# ESP32S3.net
KiCad netlist of a schematic drawn in Altium Designer
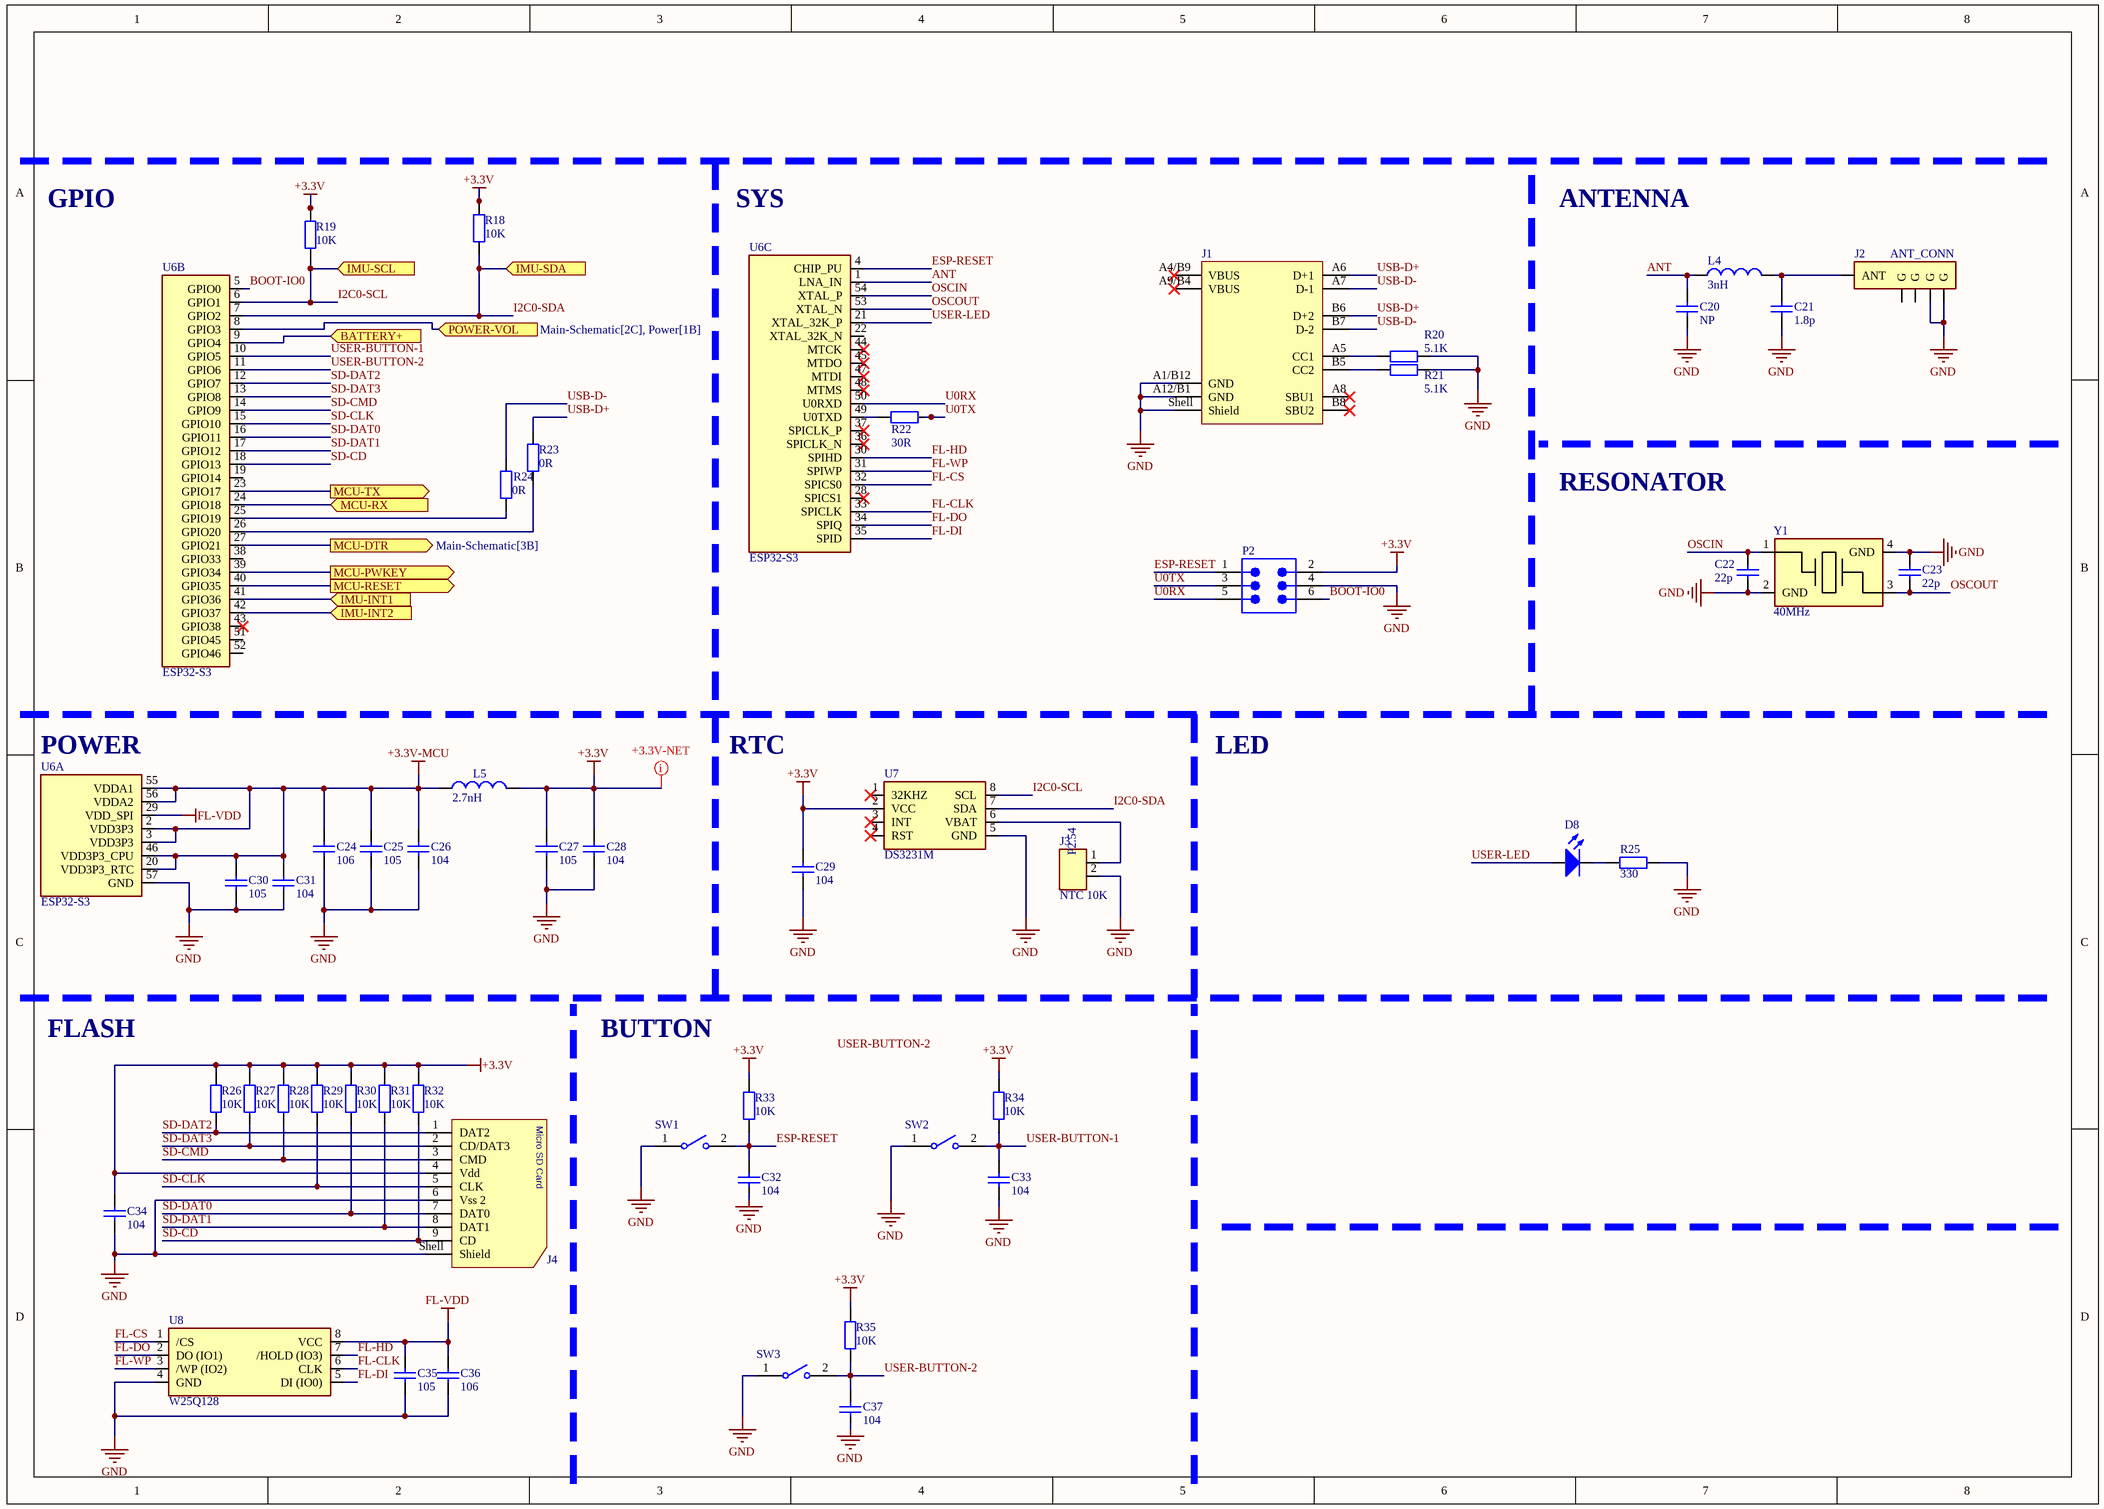
[diagram p0: ESP32S3.SchDoc]

(export (version "E")
  (design (tool "Eeschema 10.0.6"))
  (components
    (comp (ref "C20")
      (value "NP")
      (footprint "CAP_0603")
      (description "Non-polarized capacitor")
      (libsource (lib "Capacitor") (part "Cap_NP"))
    )
    (comp (ref "C21")
      (value "1.8p")
      (footprint "CAP_0603")
      (description "Non-polarized capacitor")
      (libsource (lib "Capacitor") (part "Cap_NP"))
    )
    (comp (ref "C22")
      (value "22p")
      (footprint "CAP_0603")
      (description "Non-polarized capacitor")
      (libsource (lib "Capacitor") (part "Cap_NP"))
    )
    (comp (ref "C23")
      (value "22p")
      (footprint "CAP_0603")
      (description "Non-polarized capacitor")
      (libsource (lib "Capacitor") (part "Cap_NP"))
    )
    (comp (ref "C24")
      (value "106")
      (footprint "CAP_0603")
      (description "Non-polarized capacitor")
      (libsource (lib "Capacitor") (part "Cap_NP"))
    )
    (comp (ref "C25")
      (value "105")
      (footprint "CAP_0603")
      (description "Non-polarized capacitor")
      (libsource (lib "Capacitor") (part "Cap_NP"))
    )
    (comp (ref "C26")
      (value "104")
      (footprint "CAP_0603")
      (description "Non-polarized capacitor")
      (libsource (lib "Capacitor") (part "Cap_NP"))
    )
    (comp (ref "C27")
      (value "105")
      (footprint "CAP_0603")
      (description "Non-polarized capacitor")
      (libsource (lib "Capacitor") (part "Cap_NP"))
    )
    (comp (ref "C28")
      (value "104")
      (footprint "CAP_0603")
      (description "Non-polarized capacitor")
      (libsource (lib "Capacitor") (part "Cap_NP"))
    )
    (comp (ref "C29")
      (value "104")
      (footprint "CAP_0603")
      (description "Non-polarized capacitor")
      (libsource (lib "Capacitor") (part "Cap_NP"))
    )
    (comp (ref "C30")
      (value "105")
      (footprint "CAP_0603")
      (description "Non-polarized capacitor")
      (libsource (lib "Capacitor") (part "Cap_NP"))
    )
    (comp (ref "C31")
      (value "104")
      (footprint "CAP_0603")
      (description "Non-polarized capacitor")
      (libsource (lib "Capacitor") (part "Cap_NP"))
    )
    (comp (ref "C32")
      (value "104")
      (footprint "CAP_0603")
      (description "Non-polarized capacitor")
      (libsource (lib "Capacitor") (part "Cap_NP"))
    )
    (comp (ref "C33")
      (value "104")
      (footprint "CAP_0603")
      (description "Non-polarized capacitor")
      (libsource (lib "Capacitor") (part "Cap_NP"))
    )
    (comp (ref "C34")
      (value "104")
      (footprint "CAP_0603")
      (description "Non-polarized capacitor")
      (libsource (lib "Capacitor") (part "Cap_NP"))
    )
    (comp (ref "C35")
      (value "105")
      (footprint "CAP_0603")
      (description "Non-polarized capacitor")
      (libsource (lib "Capacitor") (part "Cap_NP"))
    )
    (comp (ref "C36")
      (value "106")
      (footprint "CAP_0603")
      (description "Non-polarized capacitor")
      (libsource (lib "Capacitor") (part "Cap_NP"))
    )
    (comp (ref "C37")
      (value "104")
      (footprint "CAP_0603")
      (description "Non-polarized capacitor")
      (libsource (lib "Capacitor") (part "Cap_NP"))
    )
    (comp (ref "D8")
      (value "~")
      (footprint "LED-0805-Red")
      (description "Light Emitting Diode")
      (libsource (lib "Diode") (part "LED"))
    )
    (comp (ref "J1")
      (value "629722000214")
      (footprint "629722000214")
      (description "WR-COM USB 2.0 Type C Receptacle Horizontal SMT")
      (fields (field (name "MANUFACTURER") "Wurth Elektronik"))
      (libsource (lib "WE - Electromechanical Components") (part "USB 2.0_Type C_Receptacle_1 Port_629722000214"))
    )
    (comp (ref "J2")
      (value "ANT_CONN")
      (footprint "IPEX")
      (description "ATENNA PIN 1")
      (libsource (lib "Connector") (part "ANT_CONN"))
    )
    (comp (ref "J3")
      (value "NTC 10K")
      (footprint "XH2.54M-2")
      (libsource (lib "Connector") (part "Conn_Cai_2P_2.54"))
    )
    (comp (ref "J4")
      (value "693071040911")
      (footprint "693071040911")
      (description "WR-CRD SD Card Connector Push & Push Socket, 9 pins")
      (fields (field (name "MANUFACTURER") "Wurth Elektronik"))
      (libsource (lib "WE - Electromechanical Components") (part "Micro SD Card Socket_693071040911"))
    )
    (comp (ref "L4")
      (value "3nH")
      (footprint "INDC-0805")
      (description "Inductor")
      (fields (field (name "PUBLISHER") "Altium Limited"))
      (libsource (lib "Inductor") (part "Inductor"))
    )
    (comp (ref "L5")
      (value "2.7nH")
      (footprint "INDC-0805")
      (description "Inductor")
      (fields (field (name "PUBLISHER") "Altium Limited"))
      (libsource (lib "Inductor") (part "Inductor"))
    )
    (comp (ref "P2")
      (value "61200621621")
      (footprint "61200621621")
      (description "WR-BHD Male Box Header, THT Straight, pitch 2.54 mm, 2 Rows, 6 Pins")
      (fields (field (name "MANUFACTURER") "Wurth Elektronik"))
      (libsource (lib "WE - Electromechanical Components") (part "Header_Male_2R_06P"))
    )
    (comp (ref "R18") (value "10K") (footprint "RES_0603") (libsource (lib "Resistor") (part "Resistor")))
    (comp (ref "R19") (value "10K") (footprint "RES_0603") (libsource (lib "Resistor") (part "Resistor")))
    (comp (ref "R20") (value "5.1K") (footprint "RES_0603") (libsource (lib "") (part "Resistor_1")))
    (comp (ref "R21") (value "5.1K") (footprint "RES_0603") (libsource (lib "") (part "Resistor_1")))
    (comp (ref "R22") (value "30R") (footprint "RES_0603") (libsource (lib "") (part "Resistor_1")))
    (comp (ref "R23") (value "0R") (footprint "RES_0603") (libsource (lib "Resistor") (part "Resistor")))
    (comp (ref "R24") (value "0R") (footprint "RES_0603") (libsource (lib "Resistor") (part "Resistor")))
    (comp (ref "R25") (value "330") (footprint "RES_0603") (libsource (lib "") (part "Resistor_1")))
    (comp (ref "R26") (value "10K") (footprint "RES_0603") (libsource (lib "Resistor") (part "Resistor")))
    (comp (ref "R27") (value "10K") (footprint "RES_0603") (libsource (lib "Resistor") (part "Resistor")))
    (comp (ref "R28") (value "10K") (footprint "RES_0603") (libsource (lib "Resistor") (part "Resistor")))
    (comp (ref "R29") (value "10K") (footprint "RES_0603") (libsource (lib "Resistor") (part "Resistor")))
    (comp (ref "R30") (value "10K") (footprint "RES_0603") (libsource (lib "Resistor") (part "Resistor")))
    (comp (ref "R31") (value "10K") (footprint "RES_0603") (libsource (lib "Resistor") (part "Resistor")))
    (comp (ref "R32") (value "10K") (footprint "RES_0603") (libsource (lib "Resistor") (part "Resistor")))
    (comp (ref "R33") (value "10K") (footprint "RES_0603") (libsource (lib "Resistor") (part "Resistor")))
    (comp (ref "R34") (value "10K") (footprint "RES_0603") (libsource (lib "Resistor") (part "Resistor")))
    (comp (ref "R35") (value "10K") (footprint "RES_0603") (libsource (lib "Resistor") (part "Resistor")))
    (comp (ref "SW1")
      (value "434121050816")
      (footprint "434121050816")
      (description "WS-TASV SMT Tact Switch, 6mm x 3.5mm, 160gf, SPST-NO, 12V, 50mA")
      (fields (field (name "MANUFACTURER") "Wurth Elektronik"))
      (libsource (lib "WE - Electromechanical Components") (part "SPST-NO_2P"))
    )
    (comp (ref "SW2")
      (value "434121050816")
      (footprint "434121050816")
      (description "WS-TASV SMT Tact Switch, 6mm x 3.5mm, 160gf, SPST-NO, 12V, 50mA")
      (fields (field (name "MANUFACTURER") "Wurth Elektronik"))
      (libsource (lib "WE - Electromechanical Components") (part "SPST-NO_2P"))
    )
    (comp (ref "SW3")
      (value "434121050816")
      (footprint "434121050816")
      (description "WS-TASV SMT Tact Switch, 6mm x 3.5mm, 160gf, SPST-NO, 12V, 50mA")
      (fields (field (name "MANUFACTURER") "Wurth Elektronik"))
      (libsource (lib "WE - Electromechanical Components") (part "SPST-NO_2P"))
    )
    (comp (ref "U6") (value "ESP32-S3") (footprint "QFN56") (libsource (lib "IC") (part "ESP32-S3")))
    (comp (ref "U7")
      (value "DS3231M")
      (footprint "SOP8-P1.27")
      (description "I2C realtime clock (RTC)")
      (libsource (lib "IC") (part "DS3231M"))
    )
    (comp (ref "U8")
      (value "W25Q128")
      (footprint "SOIC127P790X216-8N")
      (description "256M-bit (32MB) Serial Flash memory")
      (libsource (lib "IC") (part "W25Q256JV"))
    )
    (comp (ref "Y1") (value "40MHz") (footprint "Y-3225") (libsource (lib "IC") (part "Resonator")))
  )
  (nets
    (net (code "1") (name "+3.3V") (class "Default")
      (node (ref "C27") (pin "2") (pinfunction "2_2") (pintype "passive"))
      (node (ref "C28") (pin "2") (pinfunction "2_2") (pintype "passive"))
      (node (ref "C29") (pin "1") (pinfunction "1_1") (pintype "passive"))
      (node (ref "C34") (pin "2") (pinfunction "2_2") (pintype "passive"))
      (node (ref "J4") (pin "4") (pinfunction "Vdd_4") (pintype "passive"))
      (node (ref "L5") (pin "2") (pinfunction "2_2") (pintype "passive"))
      (node (ref "P2") (pin "2") (pinfunction "2_2") (pintype "passive"))
      (node (ref "R18") (pin "2") (pinfunction "2_2") (pintype "passive"))
      (node (ref "R19") (pin "2") (pinfunction "2_2") (pintype "passive"))
      (node (ref "R26") (pin "2") (pinfunction "2_2") (pintype "passive"))
      (node (ref "R27") (pin "2") (pinfunction "2_2") (pintype "passive"))
      (node (ref "R28") (pin "2") (pinfunction "2_2") (pintype "passive"))
      (node (ref "R29") (pin "2") (pinfunction "2_2") (pintype "passive"))
      (node (ref "R30") (pin "2") (pinfunction "2_2") (pintype "passive"))
      (node (ref "R31") (pin "2") (pinfunction "2_2") (pintype "passive"))
      (node (ref "R32") (pin "2") (pinfunction "2_2") (pintype "passive"))
      (node (ref "R33") (pin "2") (pinfunction "2_2") (pintype "passive"))
      (node (ref "R34") (pin "2") (pinfunction "2_2") (pintype "passive"))
      (node (ref "R35") (pin "2") (pinfunction "2_2") (pintype "passive"))
      (node (ref "U7") (pin "2") (pinfunction "VCC_2") (pintype "passive"))
    )
    (net (code "2") (name "+3.3V-MCU") (class "Default")
      (node (ref "C24") (pin "2") (pinfunction "2_2") (pintype "passive"))
      (node (ref "C25") (pin "2") (pinfunction "2_2") (pintype "passive"))
      (node (ref "C26") (pin "2") (pinfunction "2_2") (pintype "passive"))
      (node (ref "C30") (pin "2") (pinfunction "2_2") (pintype "passive"))
      (node (ref "C31") (pin "2") (pinfunction "2_2") (pintype "passive"))
      (node (ref "L5") (pin "1") (pinfunction "1_1") (pintype "passive"))
      (node (ref "U6") (pin "2") (pinfunction "VDD3P3_2") (pintype "passive"))
      (node (ref "U6") (pin "20") (pinfunction "VDD3P3_RTC_20") (pintype "passive"))
      (node (ref "U6") (pin "3") (pinfunction "VDD3P3_3") (pintype "passive"))
      (node (ref "U6") (pin "46") (pinfunction "VDD3P3_CPU_46") (pintype "passive"))
      (node (ref "U6") (pin "55") (pinfunction "VDDA1_55") (pintype "passive"))
      (node (ref "U6") (pin "56") (pinfunction "VDDA2_56") (pintype "passive"))
    )
    (net (code "3") (name "/ANT") (class "Default")
      (node (ref "C20") (pin "2") (pinfunction "2_2") (pintype "passive"))
      (node (ref "L4") (pin "1") (pinfunction "1_1") (pintype "passive"))
      (node (ref "U6") (pin "1") (pinfunction "LNA_IN_1") (pintype "passive"))
    )
    (net (code "4") (name "/BATTERY+") (class "Default")
      (node (ref "U6") (pin "9") (pinfunction "GPIO4_9") (pintype "passive"))
    )
    (net (code "5") (name "/BOOT-IO0") (class "Default")
      (node (ref "P2") (pin "6") (pinfunction "6_6") (pintype "passive"))
      (node (ref "U6") (pin "5") (pinfunction "GPIO0_5") (pintype "passive"))
    )
    (net (code "6") (name "/ESP-RESET") (class "Default")
      (node (ref "C32") (pin "1") (pinfunction "1_1") (pintype "passive"))
      (node (ref "P2") (pin "1") (pinfunction "1_1") (pintype "passive"))
      (node (ref "R33") (pin "1") (pinfunction "1_1") (pintype "passive"))
      (node (ref "SW1") (pin "2") (pinfunction "2_2") (pintype "passive"))
      (node (ref "U6") (pin "4") (pinfunction "CHIP_PU_4") (pintype "passive"))
    )
    (net (code "7") (name "/FL-CLK") (class "Default")
      (node (ref "U6") (pin "33") (pinfunction "SPICLK_33") (pintype "passive"))
      (node (ref "U8") (pin "6") (pinfunction "CLK_6") (pintype "passive"))
    )
    (net (code "8") (name "/FL-CS") (class "Default")
      (node (ref "U6") (pin "32") (pinfunction "SPICS0_32") (pintype "passive"))
      (node (ref "U8") (pin "1") (pinfunction "/CS_1") (pintype "passive"))
    )
    (net (code "9") (name "/FL-DI") (class "Default")
      (node (ref "U6") (pin "35") (pinfunction "SPID_35") (pintype "passive"))
      (node (ref "U8") (pin "5") (pinfunction "DI_(IO0)_5") (pintype "passive"))
    )
    (net (code "10") (name "/FL-DO") (class "Default")
      (node (ref "U6") (pin "34") (pinfunction "SPIQ_34") (pintype "passive"))
      (node (ref "U8") (pin "2") (pinfunction "DO_(IO1)_2") (pintype "passive"))
    )
    (net (code "11") (name "/FL-HD") (class "Default")
      (node (ref "U6") (pin "30") (pinfunction "SPIHD_30") (pintype "passive"))
      (node (ref "U8") (pin "7") (pinfunction "/HOLD_(IO3)_7") (pintype "passive"))
    )
    (net (code "12") (name "/FL-WP") (class "Default")
      (node (ref "U6") (pin "31") (pinfunction "SPIWP_31") (pintype "passive"))
      (node (ref "U8") (pin "3") (pinfunction "/WP_(IO2)_3") (pintype "passive"))
    )
    (net (code "13") (name "/I2C0-SCL") (class "Default")
      (node (ref "R19") (pin "1") (pinfunction "1_1") (pintype "passive"))
      (node (ref "U6") (pin "6") (pinfunction "GPIO1_6") (pintype "passive"))
      (node (ref "U7") (pin "8") (pinfunction "SCL_8") (pintype "passive"))
    )
    (net (code "14") (name "/I2C0-SDA") (class "Default")
      (node (ref "R18") (pin "1") (pinfunction "1_1") (pintype "passive"))
      (node (ref "U6") (pin "7") (pinfunction "GPIO2_7") (pintype "passive"))
      (node (ref "U7") (pin "7") (pinfunction "SDA_7") (pintype "passive"))
    )
    (net (code "15") (name "/IMU-INT1") (class "Default")
      (node (ref "U6") (pin "41") (pinfunction "GPIO36_41") (pintype "passive"))
    )
    (net (code "16") (name "/IMU-INT2") (class "Default")
      (node (ref "U6") (pin "42") (pinfunction "GPIO37_42") (pintype "passive"))
    )
    (net (code "17") (name "/MCU-DTR") (class "Default")
      (node (ref "U6") (pin "27") (pinfunction "GPIO21_27") (pintype "passive"))
    )
    (net (code "18") (name "/MCU-PWKEY") (class "Default")
      (node (ref "U6") (pin "39") (pinfunction "GPIO34_39") (pintype "passive"))
    )
    (net (code "19") (name "/MCU-RESET") (class "Default")
      (node (ref "U6") (pin "40") (pinfunction "GPIO35_40") (pintype "passive"))
    )
    (net (code "20") (name "/MCU-RX") (class "Default")
      (node (ref "U6") (pin "24") (pinfunction "GPIO18_24") (pintype "passive"))
    )
    (net (code "21") (name "/MCU-TX") (class "Default")
      (node (ref "U6") (pin "23") (pinfunction "GPIO17_23") (pintype "passive"))
    )
    (net (code "22") (name "/OSCIN") (class "Default")
      (node (ref "C22") (pin "2") (pinfunction "2_2") (pintype "passive"))
      (node (ref "U6") (pin "54") (pinfunction "XTAL_P_54") (pintype "passive"))
      (node (ref "Y1") (pin "1") (pinfunction "OSCIN_1") (pintype "passive"))
    )
    (net (code "23") (name "/OSCOUT") (class "Default")
      (node (ref "C23") (pin "1") (pinfunction "1_1") (pintype "passive"))
      (node (ref "U6") (pin "53") (pinfunction "XTAL_N_53") (pintype "passive"))
      (node (ref "Y1") (pin "3") (pinfunction "OSCOUT_3") (pintype "passive"))
    )
    (net (code "24") (name "/POWER-VOL") (class "Default")
      (node (ref "U6") (pin "8") (pinfunction "GPIO3_8") (pintype "passive"))
    )
    (net (code "25") (name "/SD-CD") (class "Default")
      (node (ref "J4") (pin "9") (pinfunction "CD_9") (pintype "passive"))
      (node (ref "R32") (pin "1") (pinfunction "1_1") (pintype "passive"))
      (node (ref "U6") (pin "18") (pinfunction "GPIO13_18") (pintype "passive"))
    )
    (net (code "26") (name "/SD-CLK") (class "Default")
      (node (ref "J4") (pin "5") (pinfunction "CLK_5") (pintype "passive"))
      (node (ref "R29") (pin "1") (pinfunction "1_1") (pintype "passive"))
      (node (ref "U6") (pin "15") (pinfunction "GPIO10_15") (pintype "passive"))
    )
    (net (code "27") (name "/SD-CMD") (class "Default")
      (node (ref "J4") (pin "3") (pinfunction "CMD_3") (pintype "passive"))
      (node (ref "R28") (pin "1") (pinfunction "1_1") (pintype "passive"))
      (node (ref "U6") (pin "14") (pinfunction "GPIO9_14") (pintype "passive"))
    )
    (net (code "28") (name "/SD-DAT0") (class "Default")
      (node (ref "J4") (pin "7") (pinfunction "DAT0_7") (pintype "passive"))
      (node (ref "R30") (pin "1") (pinfunction "1_1") (pintype "passive"))
      (node (ref "U6") (pin "16") (pinfunction "GPIO11_16") (pintype "passive"))
    )
    (net (code "29") (name "/SD-DAT1") (class "Default")
      (node (ref "J4") (pin "8") (pinfunction "DAT1_8") (pintype "passive"))
      (node (ref "R31") (pin "1") (pinfunction "1_1") (pintype "passive"))
      (node (ref "U6") (pin "17") (pinfunction "GPIO12_17") (pintype "passive"))
    )
    (net (code "30") (name "/SD-DAT2") (class "Default")
      (node (ref "J4") (pin "1") (pinfunction "DAT2_1") (pintype "passive"))
      (node (ref "R26") (pin "1") (pinfunction "1_1") (pintype "passive"))
      (node (ref "U6") (pin "12") (pinfunction "GPIO7_12") (pintype "passive"))
    )
    (net (code "31") (name "/SD-DAT3") (class "Default")
      (node (ref "J4") (pin "2") (pinfunction "CD/DAT3_2") (pintype "passive"))
      (node (ref "R27") (pin "1") (pinfunction "1_1") (pintype "passive"))
      (node (ref "U6") (pin "13") (pinfunction "GPIO8_13") (pintype "passive"))
    )
    (net (code "32") (name "/U0RX") (class "Default")
      (node (ref "P2") (pin "5") (pinfunction "5_5") (pintype "passive"))
      (node (ref "U6") (pin "50") (pinfunction "U0RXD_50") (pintype "passive"))
    )
    (net (code "33") (name "/U0TX") (class "Default")
      (node (ref "P2") (pin "3") (pinfunction "3_3") (pintype "passive"))
      (node (ref "R22") (pin "2") (pinfunction "2_2") (pintype "passive"))
    )
    (net (code "34") (name "/USB-D+") (class "Default")
      (node (ref "J1") (pin "A6") (pinfunction "D+1_A6") (pintype "passive"))
      (node (ref "J1") (pin "B6") (pinfunction "D+2_B6") (pintype "passive"))
      (node (ref "R23") (pin "2") (pinfunction "2_2") (pintype "passive"))
    )
    (net (code "35") (name "/USB-D-") (class "Default")
      (node (ref "J1") (pin "A7") (pinfunction "D-1_A7") (pintype "passive"))
      (node (ref "J1") (pin "B7") (pinfunction "D-2_B7") (pintype "passive"))
      (node (ref "R24") (pin "2") (pinfunction "2_2") (pintype "passive"))
    )
    (net (code "36") (name "/USER-BUTTON-1") (class "Default")
      (node (ref "C33") (pin "1") (pinfunction "1_1") (pintype "passive"))
      (node (ref "R34") (pin "1") (pinfunction "1_1") (pintype "passive"))
      (node (ref "SW2") (pin "2") (pinfunction "2_2") (pintype "passive"))
      (node (ref "U6") (pin "10") (pinfunction "GPIO5_10") (pintype "passive"))
    )
    (net (code "37") (name "/USER-BUTTON-2") (class "Default")
      (node (ref "C37") (pin "1") (pinfunction "1_1") (pintype "passive"))
      (node (ref "R35") (pin "1") (pinfunction "1_1") (pintype "passive"))
      (node (ref "SW3") (pin "2") (pinfunction "2_2") (pintype "passive"))
      (node (ref "U6") (pin "11") (pinfunction "GPIO6_11") (pintype "passive"))
    )
    (net (code "38") (name "/USER-LED") (class "Default")
      (node (ref "D8") (pin "1") (pinfunction "A_1") (pintype "passive"))
      (node (ref "U6") (pin "21") (pinfunction "XTAL_32K_P_21") (pintype "passive"))
    )
    (net (code "39") (name "FL-VDD") (class "Default")
      (node (ref "C35") (pin "2") (pinfunction "2_2") (pintype "passive"))
      (node (ref "C36") (pin "2") (pinfunction "2_2") (pintype "passive"))
      (node (ref "U6") (pin "29") (pinfunction "VDD_SPI_29") (pintype "passive"))
      (node (ref "U8") (pin "8") (pinfunction "VCC_8") (pintype "passive"))
    )
    (net (code "40") (name "GND") (class "Default")
      (node (ref "C20") (pin "1") (pinfunction "1_1") (pintype "passive"))
      (node (ref "C21") (pin "1") (pinfunction "1_1") (pintype "passive"))
      (node (ref "C22") (pin "1") (pinfunction "1_1") (pintype "passive"))
      (node (ref "C23") (pin "2") (pinfunction "2_2") (pintype "passive"))
      (node (ref "C24") (pin "1") (pinfunction "1_1") (pintype "passive"))
      (node (ref "C25") (pin "1") (pinfunction "1_1") (pintype "passive"))
      (node (ref "C26") (pin "1") (pinfunction "1_1") (pintype "passive"))
      (node (ref "C27") (pin "1") (pinfunction "1_1") (pintype "passive"))
      (node (ref "C28") (pin "1") (pinfunction "1_1") (pintype "passive"))
      (node (ref "C29") (pin "2") (pinfunction "2_2") (pintype "passive"))
      (node (ref "C30") (pin "1") (pinfunction "1_1") (pintype "passive"))
      (node (ref "C31") (pin "1") (pinfunction "1_1") (pintype "passive"))
      (node (ref "C32") (pin "2") (pinfunction "2_2") (pintype "passive"))
      (node (ref "C33") (pin "2") (pinfunction "2_2") (pintype "passive"))
      (node (ref "C34") (pin "1") (pinfunction "1_1") (pintype "passive"))
      (node (ref "C35") (pin "1") (pinfunction "1_1") (pintype "passive"))
      (node (ref "C36") (pin "1") (pinfunction "1_1") (pintype "passive"))
      (node (ref "C37") (pin "2") (pinfunction "2_2") (pintype "passive"))
      (node (ref "J1") (pin "A1/B12") (pinfunction "GND_A1/B12") (pintype "passive"))
      (node (ref "J1") (pin "A12/B1") (pinfunction "GND_A12/B1") (pintype "passive"))
      (node (ref "J1") (pin "Shell") (pinfunction "Shield_Shell") (pintype "passive"))
      (node (ref "J2") (pin "4") (pinfunction "G_4") (pintype "passive"))
      (node (ref "J2") (pin "5") (pinfunction "G_5") (pintype "passive"))
      (node (ref "J3") (pin "2") (pintype "passive"))
      (node (ref "J4") (pin "6") (pinfunction "Vss_2_6") (pintype "passive"))
      (node (ref "J4") (pin "Shell") (pinfunction "Shield_Shell") (pintype "passive"))
      (node (ref "P2") (pin "4") (pinfunction "4_4") (pintype "passive"))
      (node (ref "R20") (pin "2") (pinfunction "2_2") (pintype "passive"))
      (node (ref "R21") (pin "2") (pinfunction "2_2") (pintype "passive"))
      (node (ref "R25") (pin "2") (pinfunction "2_2") (pintype "passive"))
      (node (ref "SW1") (pin "1") (pinfunction "1_1") (pintype "passive"))
      (node (ref "SW2") (pin "1") (pinfunction "1_1") (pintype "passive"))
      (node (ref "SW3") (pin "1") (pinfunction "1_1") (pintype "passive"))
      (node (ref "U6") (pin "57") (pinfunction "GND_57") (pintype "passive"))
      (node (ref "U7") (pin "5") (pinfunction "GND_5") (pintype "passive"))
      (node (ref "U8") (pin "4") (pinfunction "GND_4") (pintype "passive"))
      (node (ref "Y1") (pin "2") (pinfunction "GND_2") (pintype "passive"))
      (node (ref "Y1") (pin "4") (pinfunction "GND_4") (pintype "passive"))
    )
    (net (code "41") (name "Net-(D8-K)") (class "Default")
      (node (ref "D8") (pin "2") (pinfunction "K_2") (pintype "passive"))
      (node (ref "R25") (pin "1") (pinfunction "1_1") (pintype "passive"))
    )
    (net (code "42") (name "Net-(J1-CC1)") (class "Default")
      (node (ref "J1") (pin "A5") (pinfunction "CC1_A5") (pintype "passive"))
      (node (ref "R20") (pin "1") (pinfunction "1_1") (pintype "passive"))
    )
    (net (code "43") (name "Net-(J1-CC2)") (class "Default")
      (node (ref "J1") (pin "B5") (pinfunction "CC2_B5") (pintype "passive"))
      (node (ref "R21") (pin "1") (pinfunction "1_1") (pintype "passive"))
    )
    (net (code "44") (name "Net-(J2-ANT)") (class "Default")
      (node (ref "C21") (pin "2") (pinfunction "2_2") (pintype "passive"))
      (node (ref "J2") (pin "1") (pinfunction "ANT_1") (pintype "passive"))
      (node (ref "L4") (pin "2") (pinfunction "2_2") (pintype "passive"))
    )
    (net (code "45") (name "Net-(U6B-GPIO19)") (class "Default")
      (node (ref "R24") (pin "1") (pinfunction "1_1") (pintype "passive"))
      (node (ref "U6") (pin "25") (pinfunction "GPIO19_25") (pintype "passive"))
    )
    (net (code "46") (name "Net-(U6B-GPIO20)") (class "Default")
      (node (ref "R23") (pin "1") (pinfunction "1_1") (pintype "passive"))
      (node (ref "U6") (pin "26") (pinfunction "GPIO20_26") (pintype "passive"))
    )
    (net (code "47") (name "Net-(U6C-U0TXD)") (class "Default")
      (node (ref "R22") (pin "1") (pinfunction "1_1") (pintype "passive"))
      (node (ref "U6") (pin "49") (pinfunction "U0TXD_49") (pintype "passive"))
    )
    (net (code "48") (name "Net-(U7-VBAT)") (class "Default")
      (node (ref "J3") (pin "1") (pintype "passive"))
      (node (ref "U7") (pin "6") (pinfunction "VBAT_6") (pintype "passive"))
    )
    (net (code "49") (name "unconnected-(J1-SBU1-PadA8)") (class "Default")
      (node (ref "J1") (pin "A8") (pinfunction "SBU1_A8") (pintype "passive+no_connect"))
    )
    (net (code "50") (name "unconnected-(J1-SBU2-PadB8)") (class "Default")
      (node (ref "J1") (pin "B8") (pinfunction "SBU2_B8") (pintype "passive+no_connect"))
    )
    (net (code "51") (name "unconnected-(J1-VBUS-PadA4{slash}B9)") (class "Default")
      (node (ref "J1") (pin "A4/B9") (pinfunction "VBUS_A4/B9") (pintype "passive+no_connect"))
    )
    (net (code "52") (name "unconnected-(J1-VBUS-PadA9{slash}B4)") (class "Default")
      (node (ref "J1") (pin "A9/B4") (pinfunction "VBUS_A9/B4") (pintype "passive+no_connect"))
    )
    (net (code "53") (name "unconnected-(J2-G-Pad2)") (class "Default")
      (node (ref "J2") (pin "2") (pinfunction "G_2") (pintype "passive"))
    )
    (net (code "54") (name "unconnected-(J2-G-Pad3)") (class "Default")
      (node (ref "J2") (pin "3") (pinfunction "G_3") (pintype "passive"))
    )
    (net (code "55") (name "unconnected-(U6B-GPIO14-Pad19)") (class "Default")
      (node (ref "U6") (pin "19") (pinfunction "GPIO14_19") (pintype "passive"))
    )
    (net (code "56") (name "unconnected-(U6B-GPIO33-Pad38)") (class "Default")
      (node (ref "U6") (pin "38") (pinfunction "GPIO33_38") (pintype "passive"))
    )
    (net (code "57") (name "unconnected-(U6B-GPIO38-Pad43)") (class "Default")
      (node (ref "U6") (pin "43") (pinfunction "GPIO38_43") (pintype "passive+no_connect"))
    )
    (net (code "58") (name "unconnected-(U6B-GPIO45-Pad51)") (class "Default")
      (node (ref "U6") (pin "51") (pinfunction "GPIO45_51") (pintype "passive"))
    )
    (net (code "59") (name "unconnected-(U6B-GPIO46-Pad52)") (class "Default")
      (node (ref "U6") (pin "52") (pinfunction "GPIO46_52") (pintype "passive"))
    )
    (net (code "60") (name "unconnected-(U6C-MTCK-Pad44)") (class "Default")
      (node (ref "U6") (pin "44") (pinfunction "MTCK_44") (pintype "passive+no_connect"))
    )
    (net (code "61") (name "unconnected-(U6C-MTDI-Pad47)") (class "Default")
      (node (ref "U6") (pin "47") (pinfunction "MTDI_47") (pintype "passive+no_connect"))
    )
    (net (code "62") (name "unconnected-(U6C-MTDO-Pad45)") (class "Default")
      (node (ref "U6") (pin "45") (pinfunction "MTDO_45") (pintype "passive+no_connect"))
    )
    (net (code "63") (name "unconnected-(U6C-MTMS-Pad48)") (class "Default")
      (node (ref "U6") (pin "48") (pinfunction "MTMS_48") (pintype "passive+no_connect"))
    )
    (net (code "64") (name "unconnected-(U6C-SPICLK_N-Pad36)") (class "Default")
      (node (ref "U6") (pin "36") (pinfunction "SPICLK_N_36") (pintype "passive+no_connect"))
    )
    (net (code "65") (name "unconnected-(U6C-SPICLK_P-Pad37)") (class "Default")
      (node (ref "U6") (pin "37") (pinfunction "SPICLK_P_37") (pintype "passive+no_connect"))
    )
    (net (code "66") (name "unconnected-(U6C-SPICS1-Pad28)") (class "Default")
      (node (ref "U6") (pin "28") (pinfunction "SPICS1_28") (pintype "passive+no_connect"))
    )
    (net (code "67") (name "unconnected-(U6C-XTAL_32K_N-Pad22)") (class "Default")
      (node (ref "U6") (pin "22") (pinfunction "XTAL_32K_N_22") (pintype "passive"))
    )
    (net (code "68") (name "unconnected-(U7-32KHZ-Pad1)") (class "Default")
      (node (ref "U7") (pin "1") (pinfunction "32KHZ_1") (pintype "passive+no_connect"))
    )
    (net (code "69") (name "unconnected-(U7-INT-Pad3)") (class "Default")
      (node (ref "U7") (pin "3") (pinfunction "INT_3") (pintype "passive+no_connect"))
    )
    (net (code "70") (name "unconnected-(U7-RST-Pad4)") (class "Default")
      (node (ref "U7") (pin "4") (pinfunction "RST_4") (pintype "passive+no_connect"))
    )
  )
)
